# robotShield.net
KiCad netlist of a schematic drawn in Altium Designer
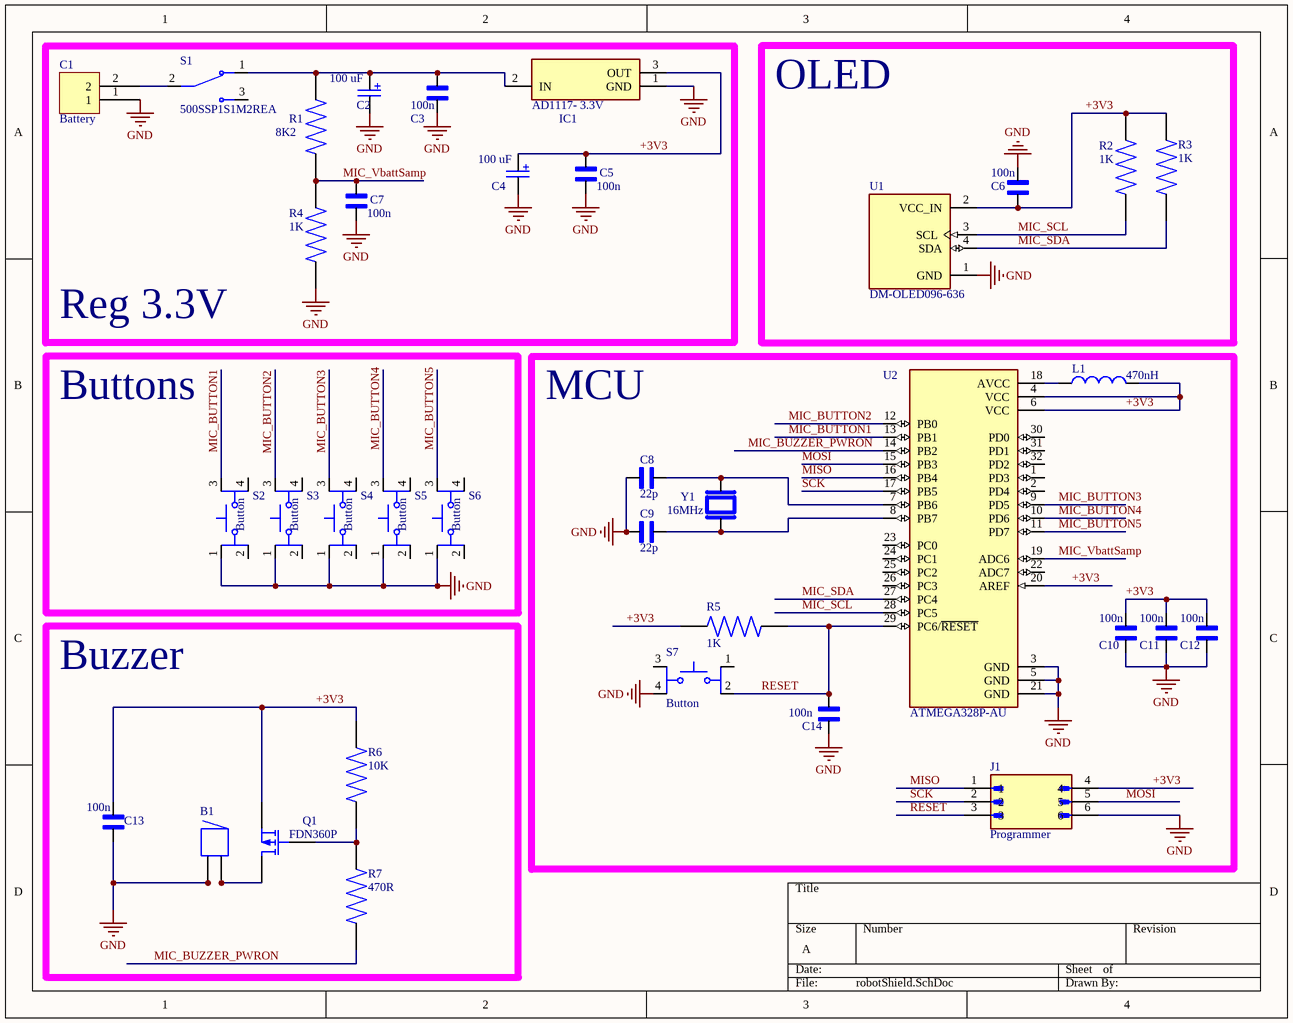
[diagram p0: robotShield.SchDoc]

(export (version "E")
  (design (tool "Eeschema 10.0.6"))
  (components
    (comp (ref "B1")
      (value "Buzzer3.3V")
      (footprint "Buzzer1")
      (description "Buzzer 5V")
      (fields (field (name "PUBLISHER") "Altium Limited"))
      (libsource (lib "Wifi_Schlib1_var1") (part "Buzzer"))
    )
    (comp (ref "C1")
      (value "Battery")
      (footprint "robotShield:Phonix2")
      (libsource (lib "robotShield") (part "Phonix2"))
    )
    (comp (ref "C2")
      (value "100 uF")
      (footprint "Cap SMD Size A Tantalium")
      (description "CAP TANT 100UF 6.3V 20% 1206")
      (fields (field (name "Comment") "F930J107MAA"))
      (libsource (lib "OK Components") (part "Capacitor"))
    )
    (comp (ref "C3")
      (value "100n")
      (footprint "CAPC2012X135N")
      (description "SMD Capacitor X5R(EIA) with Capacitance: 10uF Tol. 10%. Rated Voltage: 10Vdc")
      (fields (field (name "MF") "Murata") (field (name "MP") "GRM21BR61A106KE19K"))
      (libsource (lib "GRM21BR61A106KE19K") (part "GRM21BR61A106KE19K"))
    )
    (comp (ref "C4")
      (value "100 uF")
      (footprint "Cap SMD Size A Tantalium")
      (description "CAP TANT 100UF 6.3V 20% 1206")
      (fields (field (name "Comment") "F930J107MAA"))
      (libsource (lib "OK Components") (part "Capacitor"))
    )
    (comp (ref "C5")
      (value "100n")
      (footprint "CAPC2012X135N")
      (description "SMD Capacitor X5R(EIA) with Capacitance: 10uF Tol. 10%. Rated Voltage: 10Vdc")
      (fields (field (name "MF") "Murata") (field (name "MP") "GRM21BR61A106KE19K"))
      (libsource (lib "GRM21BR61A106KE19K") (part "GRM21BR61A106KE19K"))
    )
    (comp (ref "C6")
      (value "100n")
      (footprint "CAPC2012X135N")
      (description "SMD Capacitor X5R(EIA) with Capacitance: 10uF Tol. 10%. Rated Voltage: 10Vdc")
      (fields (field (name "MF") "Murata") (field (name "MP") "GRM21BR61A106KE19K"))
      (libsource (lib "GRM21BR61A106KE19K") (part "GRM21BR61A106KE19K"))
    )
    (comp (ref "C7")
      (value "100n")
      (footprint "CAPC2012X135N")
      (description "SMD Capacitor X5R(EIA) with Capacitance: 10uF Tol. 10%. Rated Voltage: 10Vdc")
      (fields (field (name "MF") "Murata") (field (name "MP") "GRM21BR61A106KE19K"))
      (libsource (lib "GRM21BR61A106KE19K") (part "GRM21BR61A106KE19K"))
    )
    (comp (ref "C8")
      (value "22p")
      (footprint "CAPC2012X135N")
      (description "SMD Capacitor X5R(EIA) with Capacitance: 10uF Tol. 10%. Rated Voltage: 10Vdc")
      (fields (field (name "MF") "Murata") (field (name "MP") "GRM21BR61A106KE19K"))
      (libsource (lib "") (part "GRM21BR61A106KE19K_1"))
    )
    (comp (ref "C9")
      (value "22p")
      (footprint "CAPC2012X135N")
      (description "SMD Capacitor X5R(EIA) with Capacitance: 10uF Tol. 10%. Rated Voltage: 10Vdc")
      (fields (field (name "MF") "Murata") (field (name "MP") "GRM21BR61A106KE19K"))
      (libsource (lib "") (part "GRM21BR61A106KE19K_1"))
    )
    (comp (ref "C10")
      (value "100n")
      (footprint "robotShield:CAPC2012X135N")
      (description "SMD Capacitor X5R(EIA) with Capacitance: 10uF Tol. 10%. Rated Voltage: 10Vdc")
      (fields (field (name "MF") "Murata") (field (name "MP") "GRM21BR61A106KE19K"))
      (libsource (lib "GRM21BR61A106KE19K") (part "GRM21BR61A106KE19K"))
    )
    (comp (ref "C11")
      (value "100n")
      (footprint "robotShield:CAPC2012X135N")
      (description "SMD Capacitor X5R(EIA) with Capacitance: 10uF Tol. 10%. Rated Voltage: 10Vdc")
      (fields (field (name "MF") "Murata") (field (name "MP") "GRM21BR61A106KE19K"))
      (libsource (lib "GRM21BR61A106KE19K") (part "GRM21BR61A106KE19K"))
    )
    (comp (ref "C12")
      (value "100n")
      (footprint "robotShield:CAPC2012X135N")
      (description "SMD Capacitor X5R(EIA) with Capacitance: 10uF Tol. 10%. Rated Voltage: 10Vdc")
      (fields (field (name "MF") "Murata") (field (name "MP") "GRM21BR61A106KE19K"))
      (libsource (lib "GRM21BR61A106KE19K") (part "GRM21BR61A106KE19K"))
    )
    (comp (ref "C13")
      (value "100n")
      (footprint "CAPC2012X135N")
      (description "SMD Capacitor X5R(EIA) with Capacitance: 10uF Tol. 10%. Rated Voltage: 10Vdc")
      (fields (field (name "MF") "Murata") (field (name "MP") "GRM21BR61A106KE19K"))
      (libsource (lib "GRM21BR61A106KE19K") (part "GRM21BR61A106KE19K"))
    )
    (comp (ref "C14")
      (value "100n")
      (footprint "CAPC2012X135N")
      (description "SMD Capacitor X5R(EIA) with Capacitance: 10uF Tol. 10%. Rated Voltage: 10Vdc")
      (fields (field (name "MF") "Murata") (field (name "MP") "GRM21BR61A106KE19K"))
      (libsource (lib "GRM21BR61A106KE19K") (part "GRM21BR61A106KE19K"))
    )
    (comp (ref "IC1")
      (value "AD1117- 3.3V")
      (footprint "robotShield:LD1086DT33TR")
      (description "Linear Voltage Regulator IC Positive Fixed 1 Output 1.5A DPAK")
      (fields (field (name "MF") "STMicroelectronics") (field (name "MP") "LD1086DT33TR"))
      (libsource (lib "robotShield") (part "LD1086DT33TR"))
    )
    (comp (ref "J1")
      (value "Programmer")
      (footprint "MOLEX_2068320602")
      (fields (field (name "MP") "2068320602"))
      (libsource (lib "2068320602") (part "2068320602"))
    )
    (comp (ref "L1") (value "470nH") (footprint "0805_WIDE") (libsource (lib "hadiLibrary_v3") (part "Self")))
    (comp (ref "Q1")
      (value "FDN360P")
      (footprint "SOT-23_N")
      (description "P-Channel MOSFET")
      (fields (field (name "PUBLISHER") "Altium Limited"))
      (libsource (lib "Miscellaneous Devices") (part "MOSFET-P"))
    )
    (comp (ref "R1")
      (value "8K2")
      (footprint "RESC2012X60N")
      (description "910 Ohms Â±1% 0.125W, 1/8W Chip Resistor 0805 (2012 Metric) Moisture Resistant Thick Film")
      (fields (field (name "MF") "Yageo") (field (name "MP") "RC0805FR-07910RL"))
      (libsource (lib "RC0805FR-07910RL") (part "RC0805FR-07910RL"))
    )
    (comp (ref "R2")
      (value "1K")
      (footprint "RESC2012X60N")
      (description "910 Ohms Â±1% 0.125W, 1/8W Chip Resistor 0805 (2012 Metric) Moisture Resistant Thick Film")
      (fields (field (name "MF") "Yageo") (field (name "MP") "RC0805FR-07910RL"))
      (libsource (lib "RC0805FR-07910RL") (part "RC0805FR-07910RL"))
    )
    (comp (ref "R3")
      (value "1K")
      (footprint "RESC2012X60N")
      (description "910 Ohms Â±1% 0.125W, 1/8W Chip Resistor 0805 (2012 Metric) Moisture Resistant Thick Film")
      (fields (field (name "MF") "Yageo") (field (name "MP") "RC0805FR-07910RL"))
      (libsource (lib "RC0805FR-07910RL") (part "RC0805FR-07910RL"))
    )
    (comp (ref "R4")
      (value "1K")
      (footprint "RESC2012X60N")
      (description "910 Ohms Â±1% 0.125W, 1/8W Chip Resistor 0805 (2012 Metric) Moisture Resistant Thick Film")
      (fields (field (name "MF") "Yageo") (field (name "MP") "RC0805FR-07910RL"))
      (libsource (lib "RC0805FR-07910RL") (part "RC0805FR-07910RL"))
    )
    (comp (ref "R5")
      (value "1K")
      (footprint "RESC2012X60N")
      (description "910 Ohms Â±1% 0.125W, 1/8W Chip Resistor 0805 (2012 Metric) Moisture Resistant Thick Film")
      (fields (field (name "MF") "Yageo") (field (name "MP") "RC0805FR-07910RL"))
      (libsource (lib "RC0805FR-07910RL") (part "RC0805FR-07910RL"))
    )
    (comp (ref "R6")
      (value "10K")
      (footprint "RESC2012X60N")
      (description "910 Ohms Â±1% 0.125W, 1/8W Chip Resistor 0805 (2012 Metric) Moisture Resistant Thick Film")
      (fields (field (name "MF") "Yageo") (field (name "MP") "RC0805FR-07910RL"))
      (libsource (lib "RC0805FR-07910RL") (part "RC0805FR-07910RL"))
    )
    (comp (ref "R7")
      (value "470R")
      (footprint "RESC2012X60N")
      (description "910 Ohms Â±1% 0.125W, 1/8W Chip Resistor 0805 (2012 Metric) Moisture Resistant Thick Film")
      (fields (field (name "MF") "Yageo") (field (name "MP") "RC0805FR-07910RL"))
      (libsource (lib "RC0805FR-07910RL") (part "RC0805FR-07910RL"))
    )
    (comp (ref "S1")
      (value "500SSP1S1M2REA")
      (footprint "SW_500SSP1S1M2REA")
      (libsource (lib "500SSP1S1M2REA") (part "500SSP1S1M2REA"))
    )
    (comp (ref "S2")
      (value "Button")
      (footprint "SW_TL6700AF160QG")
      (fields (field (name "MP") "TL6700AF160QG"))
      (libsource (lib "robotShield") (part "TL6700AF160QG"))
    )
    (comp (ref "S3")
      (value "Button")
      (footprint "SW_TL6700AF160QG")
      (fields (field (name "MP") "TL6700AF160QG"))
      (libsource (lib "robotShield") (part "TL6700AF160QG"))
    )
    (comp (ref "S4")
      (value "Button")
      (footprint "SW_TL6700AF160QG")
      (fields (field (name "MP") "TL6700AF160QG"))
      (libsource (lib "robotShield") (part "TL6700AF160QG"))
    )
    (comp (ref "S5")
      (value "Button")
      (footprint "SW_TL6700AF160QG")
      (fields (field (name "MP") "TL6700AF160QG"))
      (libsource (lib "robotShield") (part "TL6700AF160QG"))
    )
    (comp (ref "S6")
      (value "Button")
      (footprint "SW_TL6700AF160QG")
      (fields (field (name "MP") "TL6700AF160QG"))
      (libsource (lib "robotShield") (part "TL6700AF160QG"))
    )
    (comp (ref "S7")
      (value "Button")
      (footprint "SW_TL6700AF160QG")
      (fields (field (name "MP") "TL6700AF160QG"))
      (libsource (lib "") (part "TL6700AF160QG_1"))
    )
    (comp (ref "U1")
      (value "DM-OLED096-636")
      (footprint "MODULE_DM-OLED096-636")
      (description "0.96â€ 128 X 64 MONOCHROME GRAPHIC OLED DISPLAY MODULE - I2C")
      (fields (field (name "MF") "Display Module"))
      (libsource (lib "DM-OLED096-636") (part "DM-OLED096-636"))
    )
    (comp (ref "U2")
      (value "ATMEGA328P-AU")
      (footprint "QFP80P900X900X120-32N")
      (description "AVR AVRÂ® ATmega Microcontroller IC 8-Bit 20MHz 32KB (16K x 16) FLASH 32-TQFP (7x7)")
      (fields (field (name "MF") "Microchip Technology"))
      (libsource (lib "ATMEGA328P-AU") (part "ATMEGA328P-AU"))
    )
    (comp (ref "Y1")
      (value "16MHz")
      (footprint "XTAL_ABLS7M2-25.000MHZ-D-2Y-T")
      (description "25 MHz Â±20ppm Crystal 18pF 60 Ohms 2-SMD, Flat Lead")
      (fields (field (name "MF") "Abracon LLC") (field (name "MP") "ABLS7M2-25.000MHZ-D-2Y-T"))
      (libsource (lib "ABLS7M2-25.000MHZ-D-2Y-T") (part "ABLS7M2-25.000MHZ-D-2Y-T"))
    )
  )
  (nets
    (net (code "1") (name "/+3V3") (class "Default")
      (node (ref "C10") (pin "1") (pinfunction "1_1") (pintype "passive"))
      (node (ref "C11") (pin "1") (pinfunction "1_1") (pintype "passive"))
      (node (ref "C12") (pin "1") (pinfunction "1_1") (pintype "passive"))
      (node (ref "C13") (pin "1") (pinfunction "1_1") (pintype "passive"))
      (node (ref "C4") (pin "1") (pinfunction "+_1") (pintype "passive"))
      (node (ref "C5") (pin "1") (pinfunction "1_1") (pintype "passive"))
      (node (ref "C6") (pin "2") (pinfunction "2_2") (pintype "passive"))
      (node (ref "IC1") (pin "3") (pinfunction "OUT_3") (pintype "power_in"))
      (node (ref "J1") (pin "4") (pinfunction "4_4") (pintype "passive"))
      (node (ref "L1") (pin "2") (pinfunction "2_2") (pintype "passive"))
      (node (ref "Q1") (pin "2") (pinfunction "S_2") (pintype "passive"))
      (node (ref "R2") (pin "1") (pinfunction "1_1") (pintype "passive"))
      (node (ref "R3") (pin "2") (pinfunction "2_2") (pintype "passive"))
      (node (ref "R5") (pin "1") (pinfunction "1_1") (pintype "passive"))
      (node (ref "R6") (pin "2") (pinfunction "2_2") (pintype "passive"))
      (node (ref "U1") (pin "2") (pinfunction "VCC_IN_2") (pintype "power_in"))
      (node (ref "U2") (pin "20") (pinfunction "AREF_20") (pintype "input"))
      (node (ref "U2") (pin "4") (pinfunction "VCC_4") (pintype "power_in"))
      (node (ref "U2") (pin "6") (pinfunction "VCC_6") (pintype "power_in"))
    )
    (net (code "2") (name "/MIC_BUTTON1") (class "Default")
      (node (ref "S2") (pin "3") (pinfunction "3_3") (pintype "passive"))
      (node (ref "U2") (pin "13") (pinfunction "PB1_13") (pintype "bidirectional"))
    )
    (net (code "3") (name "/MIC_BUTTON2") (class "Default")
      (node (ref "S3") (pin "3") (pinfunction "3_3") (pintype "passive"))
      (node (ref "U2") (pin "12") (pinfunction "PB0_12") (pintype "bidirectional"))
    )
    (net (code "4") (name "/MIC_BUTTON3") (class "Default")
      (node (ref "S4") (pin "3") (pinfunction "3_3") (pintype "passive"))
      (node (ref "U2") (pin "9") (pinfunction "PD5_9") (pintype "bidirectional"))
    )
    (net (code "5") (name "/MIC_BUTTON4") (class "Default")
      (node (ref "S5") (pin "3") (pinfunction "3_3") (pintype "passive"))
      (node (ref "U2") (pin "10") (pinfunction "PD6_10") (pintype "bidirectional"))
    )
    (net (code "6") (name "/MIC_BUTTON5") (class "Default")
      (node (ref "S6") (pin "3") (pinfunction "3_3") (pintype "passive"))
      (node (ref "U2") (pin "11") (pinfunction "PD7_11") (pintype "bidirectional"))
    )
    (net (code "7") (name "/MIC_BUZZER_PWRON") (class "Default")
      (node (ref "R7") (pin "1") (pinfunction "1_1") (pintype "passive"))
      (node (ref "U2") (pin "14") (pinfunction "PB2_14") (pintype "bidirectional"))
    )
    (net (code "8") (name "/MIC_SCL") (class "Default")
      (node (ref "R2") (pin "2") (pinfunction "2_2") (pintype "passive"))
      (node (ref "U1") (pin "3") (pinfunction "SCL_3") (pintype "input"))
      (node (ref "U2") (pin "28") (pinfunction "PC5_28") (pintype "bidirectional"))
    )
    (net (code "9") (name "/MIC_SDA") (class "Default")
      (node (ref "R3") (pin "1") (pinfunction "1_1") (pintype "passive"))
      (node (ref "U1") (pin "4") (pinfunction "SDA_4") (pintype "bidirectional"))
      (node (ref "U2") (pin "27") (pinfunction "PC4_27") (pintype "bidirectional"))
    )
    (net (code "10") (name "/MIC_VbattSamp") (class "Default")
      (node (ref "C7") (pin "1") (pinfunction "1_1") (pintype "passive"))
      (node (ref "R1") (pin "1") (pinfunction "1_1") (pintype "passive"))
      (node (ref "R4") (pin "2") (pinfunction "2_2") (pintype "passive"))
      (node (ref "U2") (pin "19") (pinfunction "ADC6_19") (pintype "bidirectional"))
    )
    (net (code "11") (name "/MISO") (class "Default")
      (node (ref "J1") (pin "1") (pinfunction "1_1") (pintype "passive"))
      (node (ref "U2") (pin "16") (pinfunction "PB4_16") (pintype "bidirectional"))
    )
    (net (code "12") (name "/MOSI") (class "Default")
      (node (ref "J1") (pin "5") (pinfunction "5_5") (pintype "passive"))
      (node (ref "U2") (pin "15") (pinfunction "PB3_15") (pintype "bidirectional"))
    )
    (net (code "13") (name "/RESET") (class "Default")
      (node (ref "C14") (pin "1") (pinfunction "1_1") (pintype "passive"))
      (node (ref "J1") (pin "3") (pinfunction "3_3") (pintype "passive"))
      (node (ref "R5") (pin "2") (pinfunction "2_2") (pintype "passive"))
      (node (ref "S7") (pin "2") (pinfunction "2_2") (pintype "passive"))
      (node (ref "U2") (pin "29") (pinfunction "PC6/~{RESET}_29") (pintype "bidirectional"))
    )
    (net (code "14") (name "/SCK") (class "Default")
      (node (ref "J1") (pin "2") (pinfunction "2_2") (pintype "passive"))
      (node (ref "U2") (pin "17") (pinfunction "PB5_17") (pintype "bidirectional"))
    )
    (net (code "15") (name "GND") (class "Default")
      (node (ref "B1") (pin "2") (pinfunction "2_2") (pintype "passive"))
      (node (ref "B1") (pin "2A") (pinfunction "2A_2A") (pintype "passive"))
      (node (ref "C1") (pin "1") (pinfunction "1_1") (pintype "passive"))
      (node (ref "C10") (pin "2") (pinfunction "2_2") (pintype "passive"))
      (node (ref "C11") (pin "2") (pinfunction "2_2") (pintype "passive"))
      (node (ref "C12") (pin "2") (pinfunction "2_2") (pintype "passive"))
      (node (ref "C13") (pin "2") (pinfunction "2_2") (pintype "passive"))
      (node (ref "C14") (pin "2") (pinfunction "2_2") (pintype "passive"))
      (node (ref "C2") (pin "2") (pinfunction "-_2") (pintype "passive"))
      (node (ref "C3") (pin "2") (pinfunction "2_2") (pintype "passive"))
      (node (ref "C4") (pin "2") (pinfunction "-_2") (pintype "passive"))
      (node (ref "C5") (pin "2") (pinfunction "2_2") (pintype "passive"))
      (node (ref "C6") (pin "1") (pinfunction "1_1") (pintype "passive"))
      (node (ref "C7") (pin "2") (pinfunction "2_2") (pintype "passive"))
      (node (ref "C8") (pin "1") (pinfunction "1_1") (pintype "passive"))
      (node (ref "C9") (pin "1") (pinfunction "1_1") (pintype "passive"))
      (node (ref "IC1") (pin "1") (pinfunction "GND_1") (pintype "power_in"))
      (node (ref "J1") (pin "6") (pinfunction "6_6") (pintype "passive"))
      (node (ref "R4") (pin "1") (pinfunction "1_1") (pintype "passive"))
      (node (ref "S2") (pin "1") (pinfunction "1_1") (pintype "passive"))
      (node (ref "S3") (pin "1") (pinfunction "1_1") (pintype "passive"))
      (node (ref "S4") (pin "1") (pinfunction "1_1") (pintype "passive"))
      (node (ref "S5") (pin "1") (pinfunction "1_1") (pintype "passive"))
      (node (ref "S6") (pin "1") (pinfunction "1_1") (pintype "passive"))
      (node (ref "S7") (pin "4") (pinfunction "4_4") (pintype "passive"))
      (node (ref "U1") (pin "1") (pinfunction "GND_1") (pintype "power_in"))
      (node (ref "U2") (pin "21") (pinfunction "GND_21") (pintype "power_in"))
      (node (ref "U2") (pin "3") (pinfunction "GND_3") (pintype "power_in"))
      (node (ref "U2") (pin "5") (pinfunction "GND_5") (pintype "power_in"))
    )
    (net (code "16") (name "Net-(C2-+)") (class "Default")
      (node (ref "C2") (pin "1") (pinfunction "+_1") (pintype "passive"))
      (node (ref "C3") (pin "1") (pinfunction "1_1") (pintype "passive"))
      (node (ref "IC1") (pin "2") (pinfunction "IN_2") (pintype "power_in"))
      (node (ref "R1") (pin "2") (pinfunction "2_2") (pintype "passive"))
      (node (ref "S1") (pin "1") (pinfunction "NC_1") (pintype "passive"))
    )
    (net (code "17") (name "Net-(Q1-D)") (class "Default")
      (node (ref "B1") (pin "1") (pinfunction "1_1") (pintype "passive"))
      (node (ref "B1") (pin "1A") (pinfunction "1A_1A") (pintype "passive"))
      (node (ref "Q1") (pin "3") (pinfunction "D_3") (pintype "passive"))
    )
    (net (code "18") (name "Net-(Q1-G)") (class "Default")
      (node (ref "Q1") (pin "1") (pinfunction "G_1") (pintype "passive"))
      (node (ref "R6") (pin "1") (pinfunction "1_1") (pintype "passive"))
      (node (ref "R7") (pin "2") (pinfunction "2_2") (pintype "passive"))
    )
    (net (code "19") (name "Net-(S1-COM)") (class "Default")
      (node (ref "C1") (pin "2") (pinfunction "2_2") (pintype "passive"))
      (node (ref "S1") (pin "2") (pinfunction "COM_2") (pintype "passive"))
    )
    (net (code "20") (name "Net-(U2-AVCC)") (class "Default")
      (node (ref "L1") (pin "1") (pinfunction "1_1") (pintype "passive"))
      (node (ref "U2") (pin "18") (pinfunction "AVCC_18") (pintype "power_in"))
    )
    (net (code "21") (name "Net-(U2-PB6)") (class "Default")
      (node (ref "C8") (pin "2") (pinfunction "2_2") (pintype "passive"))
      (node (ref "U2") (pin "7") (pinfunction "PB6_7") (pintype "bidirectional"))
      (node (ref "Y1") (pin "2") (pinfunction "2_2") (pintype "passive"))
    )
    (net (code "22") (name "Net-(U2-PB7)") (class "Default")
      (node (ref "C9") (pin "2") (pinfunction "2_2") (pintype "passive"))
      (node (ref "U2") (pin "8") (pinfunction "PB7_8") (pintype "bidirectional"))
      (node (ref "Y1") (pin "1") (pinfunction "1_1") (pintype "passive"))
    )
    (net (code "23") (name "unconnected-(S1-NO-Pad3)") (class "Default")
      (node (ref "S1") (pin "3") (pinfunction "NO_3") (pintype "passive"))
    )
    (net (code "24") (name "unconnected-(S2-Pad2)") (class "Default")
      (node (ref "S2") (pin "2") (pinfunction "2_2") (pintype "passive"))
    )
    (net (code "25") (name "unconnected-(S2-Pad4)") (class "Default")
      (node (ref "S2") (pin "4") (pinfunction "4_4") (pintype "passive"))
    )
    (net (code "26") (name "unconnected-(S3-Pad2)") (class "Default")
      (node (ref "S3") (pin "2") (pinfunction "2_2") (pintype "passive"))
    )
    (net (code "27") (name "unconnected-(S3-Pad4)") (class "Default")
      (node (ref "S3") (pin "4") (pinfunction "4_4") (pintype "passive"))
    )
    (net (code "28") (name "unconnected-(S4-Pad2)") (class "Default")
      (node (ref "S4") (pin "2") (pinfunction "2_2") (pintype "passive"))
    )
    (net (code "29") (name "unconnected-(S4-Pad4)") (class "Default")
      (node (ref "S4") (pin "4") (pinfunction "4_4") (pintype "passive"))
    )
    (net (code "30") (name "unconnected-(S5-Pad2)") (class "Default")
      (node (ref "S5") (pin "2") (pinfunction "2_2") (pintype "passive"))
    )
    (net (code "31") (name "unconnected-(S5-Pad4)") (class "Default")
      (node (ref "S5") (pin "4") (pinfunction "4_4") (pintype "passive"))
    )
    (net (code "32") (name "unconnected-(S6-Pad2)") (class "Default")
      (node (ref "S6") (pin "2") (pinfunction "2_2") (pintype "passive"))
    )
    (net (code "33") (name "unconnected-(S6-Pad4)") (class "Default")
      (node (ref "S6") (pin "4") (pinfunction "4_4") (pintype "passive"))
    )
    (net (code "34") (name "unconnected-(S7-Pad1)") (class "Default")
      (node (ref "S7") (pin "1") (pinfunction "1_1") (pintype "passive"))
    )
    (net (code "35") (name "unconnected-(S7-Pad3)") (class "Default")
      (node (ref "S7") (pin "3") (pinfunction "3_3") (pintype "passive"))
    )
    (net (code "36") (name "unconnected-(U2-ADC7-Pad22)") (class "Default")
      (node (ref "U2") (pin "22") (pinfunction "ADC7_22") (pintype "bidirectional"))
    )
    (net (code "37") (name "unconnected-(U2-PC0-Pad23)") (class "Default")
      (node (ref "U2") (pin "23") (pinfunction "PC0_23") (pintype "bidirectional"))
    )
    (net (code "38") (name "unconnected-(U2-PC1-Pad24)") (class "Default")
      (node (ref "U2") (pin "24") (pinfunction "PC1_24") (pintype "bidirectional"))
    )
    (net (code "39") (name "unconnected-(U2-PC2-Pad25)") (class "Default")
      (node (ref "U2") (pin "25") (pinfunction "PC2_25") (pintype "bidirectional"))
    )
    (net (code "40") (name "unconnected-(U2-PC3-Pad26)") (class "Default")
      (node (ref "U2") (pin "26") (pinfunction "PC3_26") (pintype "bidirectional"))
    )
    (net (code "41") (name "unconnected-(U2-PD0-Pad30)") (class "Default")
      (node (ref "U2") (pin "30") (pinfunction "PD0_30") (pintype "bidirectional"))
    )
    (net (code "42") (name "unconnected-(U2-PD1-Pad31)") (class "Default")
      (node (ref "U2") (pin "31") (pinfunction "PD1_31") (pintype "bidirectional"))
    )
    (net (code "43") (name "unconnected-(U2-PD2-Pad32)") (class "Default")
      (node (ref "U2") (pin "32") (pinfunction "PD2_32") (pintype "bidirectional"))
    )
    (net (code "44") (name "unconnected-(U2-PD3-Pad1)") (class "Default")
      (node (ref "U2") (pin "1") (pinfunction "PD3_1") (pintype "bidirectional"))
    )
    (net (code "45") (name "unconnected-(U2-PD4-Pad2)") (class "Default")
      (node (ref "U2") (pin "2") (pinfunction "PD4_2") (pintype "bidirectional"))
    )
  )
)
